# MCU.net
KiCad netlist of a schematic drawn in Altium Designer
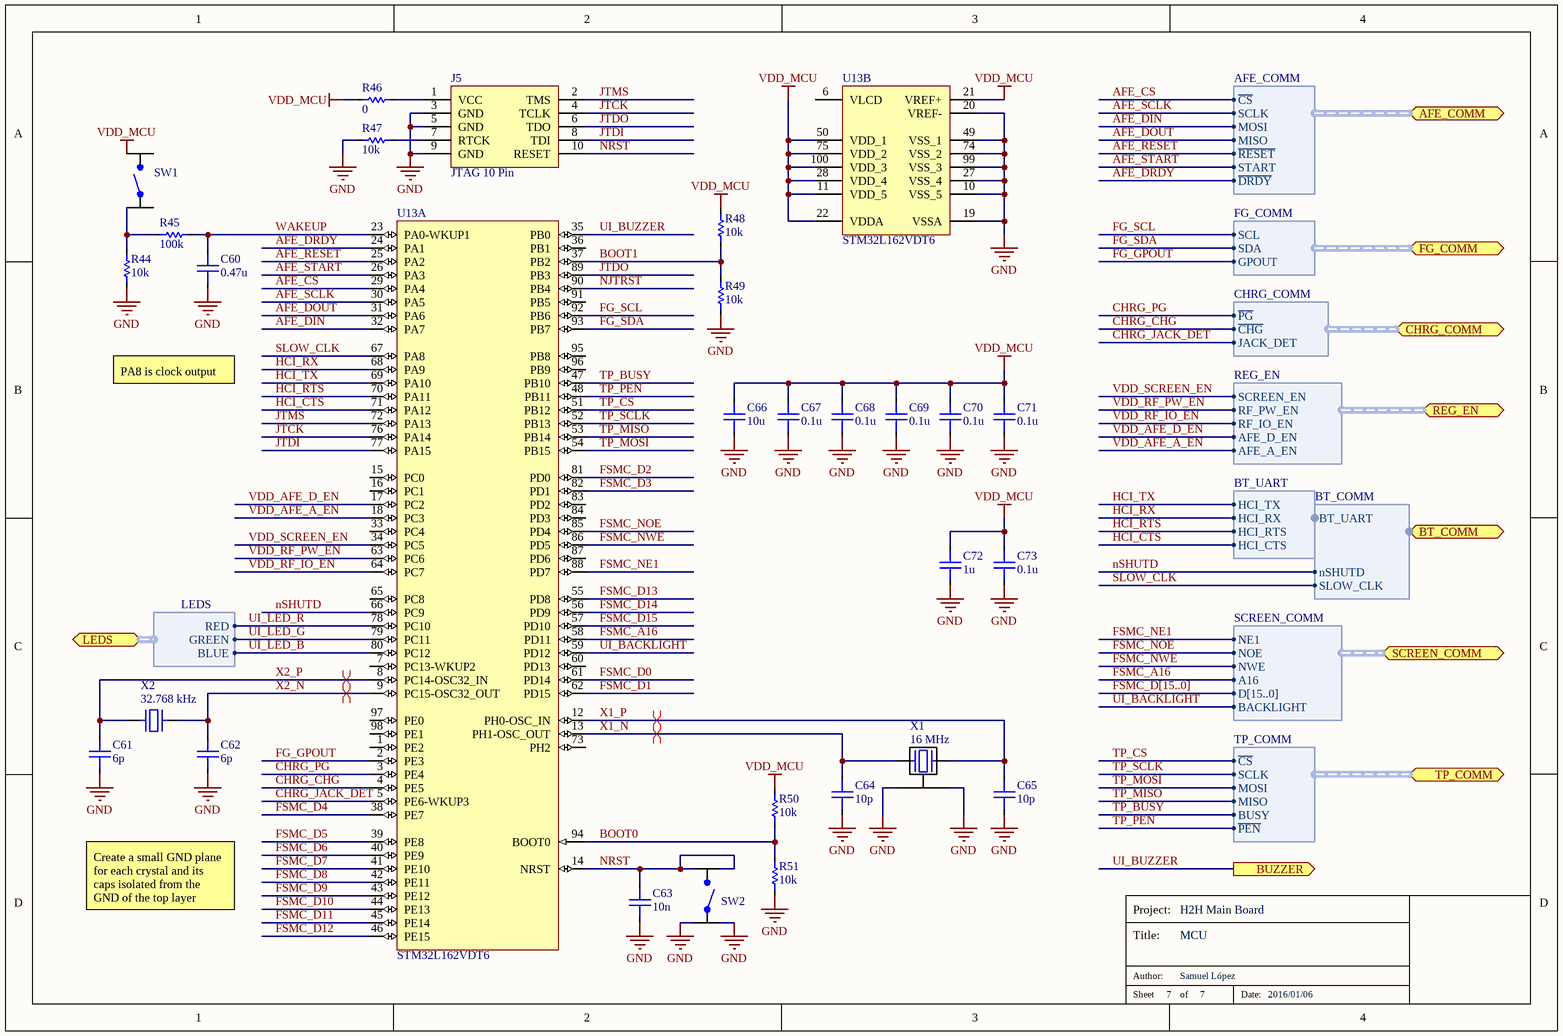
[diagram p0: MCU.SchDoc]

(export (version "E")
  (design (tool "Eeschema 10.0.6"))
  (components
    (comp (ref "C60")
      (value "0.47u")
      (footprint "C0603")
      (description "Capacitor")
      (libsource (lib "Misc") (part "Capacitor"))
    )
    (comp (ref "C61")
      (value "6p")
      (footprint "C0603")
      (description "Capacitor")
      (libsource (lib "Misc") (part "Capacitor"))
    )
    (comp (ref "C62")
      (value "6p")
      (footprint "C0603")
      (description "Capacitor")
      (libsource (lib "Misc") (part "Capacitor"))
    )
    (comp (ref "C63")
      (value "10n")
      (footprint "C0603")
      (description "Capacitor")
      (libsource (lib "Misc") (part "Capacitor"))
    )
    (comp (ref "C64")
      (value "10p")
      (footprint "C0603")
      (description "Capacitor")
      (libsource (lib "Misc") (part "Capacitor"))
    )
    (comp (ref "C65")
      (value "10p")
      (footprint "C0603")
      (description "Capacitor")
      (libsource (lib "Misc") (part "Capacitor"))
    )
    (comp (ref "C66")
      (value "10u")
      (footprint "C0603")
      (description "Capacitor")
      (libsource (lib "Misc") (part "Capacitor"))
    )
    (comp (ref "C67")
      (value "0.1u")
      (footprint "C0603")
      (description "Capacitor")
      (libsource (lib "Misc") (part "Capacitor"))
    )
    (comp (ref "C68")
      (value "0.1u")
      (footprint "C0603")
      (description "Capacitor")
      (libsource (lib "Misc") (part "Capacitor"))
    )
    (comp (ref "C69")
      (value "0.1u")
      (footprint "C0603")
      (description "Capacitor")
      (libsource (lib "Misc") (part "Capacitor"))
    )
    (comp (ref "C70")
      (value "0.1u")
      (footprint "C0603")
      (description "Capacitor")
      (libsource (lib "Misc") (part "Capacitor"))
    )
    (comp (ref "C71")
      (value "0.1u")
      (footprint "C0603")
      (description "Capacitor")
      (libsource (lib "Misc") (part "Capacitor"))
    )
    (comp (ref "C72")
      (value "1u")
      (footprint "C0603")
      (description "Capacitor")
      (libsource (lib "Misc") (part "Capacitor"))
    )
    (comp (ref "C73")
      (value "0.1u")
      (footprint "C0603")
      (description "Capacitor")
      (libsource (lib "Misc") (part "Capacitor"))
    )
    (comp (ref "J5")
      (value "JTAG 10 Pin")
      (footprint "3220-10-0200-00")
      (description "Conn - JTAG, Header, Male, Right Angle, 10 Pin, 1.27mm Pitch, ARM Standard")
      (libsource (lib "Conn") (part "3220-10-0200-00"))
    )
    (comp (ref "R44")
      (value "10k")
      (footprint "R0603")
      (description "Resistor")
      (libsource (lib "Misc") (part "Resistor"))
    )
    (comp (ref "R45")
      (value "100k")
      (footprint "R0603")
      (description "Resistor")
      (libsource (lib "Misc") (part "Resistor"))
    )
    (comp (ref "R46")
      (value "0")
      (footprint "R0603")
      (description "Resistor")
      (libsource (lib "Misc") (part "Resistor"))
    )
    (comp (ref "R47")
      (value "10k")
      (footprint "R0603")
      (description "Resistor")
      (libsource (lib "Misc") (part "Resistor"))
    )
    (comp (ref "R48")
      (value "10k")
      (footprint "R0603")
      (description "Resistor")
      (libsource (lib "Misc") (part "Resistor"))
    )
    (comp (ref "R49")
      (value "10k")
      (footprint "R0603")
      (description "Resistor")
      (libsource (lib "Misc") (part "Resistor"))
    )
    (comp (ref "R50")
      (value "10k")
      (footprint "R0603")
      (description "Resistor")
      (libsource (lib "Misc") (part "Resistor"))
    )
    (comp (ref "R51")
      (value "10k")
      (footprint "R0603")
      (description "Resistor")
      (libsource (lib "Misc") (part "Resistor"))
    )
    (comp (ref "SW1")
      (value "WS-TASU 436331045822")
      (footprint "WS-TASU 436331045822")
      (description "Switch - Tactile, Off-Mom, SPST, Side-Actuated")
      (libsource (lib "H2H") (part "WS-TASU 436331045822"))
    )
    (comp (ref "SW2")
      (value "EVQ-Q2K01W")
      (footprint "EVQ-Q2K01W")
      (description "Switch - Tactile, Off-Mom, SPST")
      (libsource (lib "H2H") (part "EVQ-Q2K01W"))
    )
    (comp (ref "U13")
      (value "STM32L162VDT6")
      (footprint "STM-LQFP100_N")
      (fields (field (name "MANUFACTURER") "STMicroelectronics"))
      (libsource (lib "STMicroelectronics STM32 L1") (part "STM32L162VDT6"))
    )
    (comp (ref "X1")
      (value "ABM3B-16.000MHZ-10-1-U")
      (footprint "ABM3B-16.000MHZ-10-1-U")
      (description "Crystal - 16 MHz")
      (fields (field (name "FREQUENCY") "16 MHz"))
      (libsource (lib "H2H") (part "ABM3B-16.000MHZ-10-1-U"))
    )
    (comp (ref "X2")
      (value "ABS07-120-32.768KHZ-T")
      (footprint "ABS07-120-32.768KHZ-T")
      (description "Crystal - 32.768 kHz")
      (fields (field (name "FREQUENCY") "32.768 kHz"))
      (libsource (lib "H2H") (part "ABS07-120-32.768KHZ-T"))
    )
  )
  (nets
    (net (code "9") (name "/AFE_CS") (class "Default")
      (node (ref "U13") (pin "29") (pinfunction "PA4_29") (pintype "bidirectional"))
    )
    (net (code "10") (name "/AFE_DIN") (class "Default")
      (node (ref "U13") (pin "32") (pinfunction "PA7_32") (pintype "bidirectional"))
    )
    (net (code "11") (name "/AFE_DOUT") (class "Default")
      (node (ref "U13") (pin "31") (pinfunction "PA6_31") (pintype "bidirectional"))
    )
    (net (code "12") (name "/AFE_DRDY") (class "Default")
      (node (ref "U13") (pin "24") (pinfunction "PA1_24") (pintype "bidirectional"))
    )
    (net (code "13") (name "/AFE_RESET") (class "Default")
      (node (ref "U13") (pin "25") (pinfunction "PA2_25") (pintype "bidirectional"))
    )
    (net (code "14") (name "/AFE_SCLK") (class "Default")
      (node (ref "U13") (pin "30") (pinfunction "PA5_30") (pintype "bidirectional"))
    )
    (net (code "15") (name "/AFE_START") (class "Default")
      (node (ref "U13") (pin "26") (pinfunction "PA3_26") (pintype "bidirectional"))
    )
    (net (code "16") (name "/BOOT0") (class "Default")
      (node (ref "R50") (pin "1") (pinfunction "1_1") (pintype "passive"))
      (node (ref "R51") (pin "2") (pinfunction "2_2") (pintype "passive"))
      (node (ref "U13") (pin "94") (pinfunction "BOOT0_94") (pintype "input"))
    )
    (net (code "17") (name "/BOOT1") (class "Default")
      (node (ref "R48") (pin "1") (pinfunction "1_1") (pintype "passive"))
      (node (ref "R49") (pin "2") (pinfunction "2_2") (pintype "passive"))
      (node (ref "U13") (pin "37") (pinfunction "PB2_37") (pintype "bidirectional"))
    )
    (net (code "18") (name "/CHRG_CHG") (class "Default")
      (node (ref "U13") (pin "4") (pinfunction "PE5_4") (pintype "bidirectional"))
    )
    (net (code "19") (name "/CHRG_JACK_DET") (class "Default")
      (node (ref "U13") (pin "5") (pinfunction "PE6-WKUP3_5") (pintype "bidirectional"))
    )
    (net (code "20") (name "/CHRG_PG") (class "Default")
      (node (ref "U13") (pin "3") (pinfunction "PE4_3") (pintype "bidirectional"))
    )
    (net (code "21") (name "/FG_GPOUT") (class "Default")
      (node (ref "U13") (pin "2") (pinfunction "PE3_2") (pintype "bidirectional"))
    )
    (net (code "22") (name "/FG_SCL") (class "Default")
      (node (ref "U13") (pin "92") (pinfunction "PB6_92") (pintype "bidirectional"))
    )
    (net (code "23") (name "/FG_SDA") (class "Default")
      (node (ref "U13") (pin "93") (pinfunction "PB7_93") (pintype "bidirectional"))
    )
    (net (code "24") (name "/FSMC_A16") (class "Default")
      (node (ref "U13") (pin "58") (pinfunction "PD11_58") (pintype "bidirectional"))
    )
    (net (code "25") (name "/FSMC_D0") (class "Default")
      (node (ref "U13") (pin "61") (pinfunction "PD14_61") (pintype "bidirectional"))
    )
    (net (code "26") (name "/FSMC_D1") (class "Default")
      (node (ref "U13") (pin "62") (pinfunction "PD15_62") (pintype "bidirectional"))
    )
    (net (code "27") (name "/FSMC_D2") (class "Default")
      (node (ref "U13") (pin "81") (pinfunction "PD0_81") (pintype "bidirectional"))
    )
    (net (code "28") (name "/FSMC_D3") (class "Default")
      (node (ref "U13") (pin "82") (pinfunction "PD1_82") (pintype "bidirectional"))
    )
    (net (code "29") (name "/FSMC_D4") (class "Default")
      (node (ref "U13") (pin "38") (pinfunction "PE7_38") (pintype "bidirectional"))
    )
    (net (code "30") (name "/FSMC_D5") (class "Default")
      (node (ref "U13") (pin "39") (pinfunction "PE8_39") (pintype "bidirectional"))
    )
    (net (code "31") (name "/FSMC_D6") (class "Default")
      (node (ref "U13") (pin "40") (pinfunction "PE9_40") (pintype "bidirectional"))
    )
    (net (code "32") (name "/FSMC_D7") (class "Default")
      (node (ref "U13") (pin "41") (pinfunction "PE10_41") (pintype "bidirectional"))
    )
    (net (code "33") (name "/FSMC_D8") (class "Default")
      (node (ref "U13") (pin "42") (pinfunction "PE11_42") (pintype "bidirectional"))
    )
    (net (code "34") (name "/FSMC_D9") (class "Default")
      (node (ref "U13") (pin "43") (pinfunction "PE12_43") (pintype "bidirectional"))
    )
    (net (code "35") (name "/FSMC_D10") (class "Default")
      (node (ref "U13") (pin "44") (pinfunction "PE13_44") (pintype "bidirectional"))
    )
    (net (code "36") (name "/FSMC_D11") (class "Default")
      (node (ref "U13") (pin "45") (pinfunction "PE14_45") (pintype "bidirectional"))
    )
    (net (code "37") (name "/FSMC_D12") (class "Default")
      (node (ref "U13") (pin "46") (pinfunction "PE15_46") (pintype "bidirectional"))
    )
    (net (code "38") (name "/FSMC_D13") (class "Default")
      (node (ref "U13") (pin "55") (pinfunction "PD8_55") (pintype "bidirectional"))
    )
    (net (code "39") (name "/FSMC_D14") (class "Default")
      (node (ref "U13") (pin "56") (pinfunction "PD9_56") (pintype "bidirectional"))
    )
    (net (code "40") (name "/FSMC_D15") (class "Default")
      (node (ref "U13") (pin "57") (pinfunction "PD10_57") (pintype "bidirectional"))
    )
    (net (code "41") (name "/FSMC_NE1") (class "Default")
      (node (ref "U13") (pin "88") (pinfunction "PD7_88") (pintype "bidirectional"))
    )
    (net (code "42") (name "/FSMC_NOE") (class "Default")
      (node (ref "U13") (pin "85") (pinfunction "PD4_85") (pintype "bidirectional"))
    )
    (net (code "43") (name "/FSMC_NWE") (class "Default")
      (node (ref "U13") (pin "86") (pinfunction "PD5_86") (pintype "bidirectional"))
    )
    (net (code "44") (name "/HCI_CTS") (class "Default")
      (node (ref "U13") (pin "71") (pinfunction "PA12_71") (pintype "bidirectional"))
    )
    (net (code "45") (name "/HCI_RTS") (class "Default")
      (node (ref "U13") (pin "70") (pinfunction "PA11_70") (pintype "bidirectional"))
    )
    (net (code "46") (name "/HCI_RX") (class "Default")
      (node (ref "U13") (pin "68") (pinfunction "PA9_68") (pintype "bidirectional"))
    )
    (net (code "47") (name "/HCI_TX") (class "Default")
      (node (ref "U13") (pin "69") (pinfunction "PA10_69") (pintype "bidirectional"))
    )
    (net (code "48") (name "/JTCK") (class "Default")
      (node (ref "J5") (pin "4") (pinfunction "TCLK_4") (pintype "passive"))
      (node (ref "U13") (pin "76") (pinfunction "PA14_76") (pintype "bidirectional"))
    )
    (net (code "49") (name "/JTDI") (class "Default")
      (node (ref "J5") (pin "8") (pinfunction "TDI_8") (pintype "passive"))
      (node (ref "U13") (pin "77") (pinfunction "PA15_77") (pintype "bidirectional"))
    )
    (net (code "50") (name "/JTDO") (class "Default")
      (node (ref "J5") (pin "6") (pinfunction "TDO_6") (pintype "passive"))
      (node (ref "U13") (pin "89") (pinfunction "PB3_89") (pintype "bidirectional"))
    )
    (net (code "51") (name "/JTMS") (class "Default")
      (node (ref "J5") (pin "2") (pinfunction "TMS_2") (pintype "passive"))
      (node (ref "U13") (pin "72") (pinfunction "PA13_72") (pintype "bidirectional"))
    )
    (net (code "52") (name "/NJTRST") (class "Default")
      (node (ref "U13") (pin "90") (pinfunction "PB4_90") (pintype "bidirectional"))
    )
    (net (code "53") (name "/NRST") (class "Default")
      (node (ref "C63") (pin "2") (pinfunction "2_2") (pintype "passive"))
      (node (ref "J5") (pin "10") (pinfunction "RESET_10") (pintype "passive"))
      (node (ref "SW2") (pin "3") (pinfunction "B2_3") (pintype "passive"))
      (node (ref "SW2") (pin "4") (pinfunction "B1_4") (pintype "passive"))
      (node (ref "U13") (pin "14") (pinfunction "NRST_14") (pintype "bidirectional"))
    )
    (net (code "55") (name "/SLOW_CLK") (class "Default")
      (node (ref "U13") (pin "67") (pinfunction "PA8_67") (pintype "bidirectional"))
    )
    (net (code "56") (name "/TP_BUSY") (class "Default")
      (node (ref "U13") (pin "47") (pinfunction "PB10_47") (pintype "bidirectional"))
    )
    (net (code "57") (name "/TP_CS") (class "Default")
      (node (ref "U13") (pin "51") (pinfunction "PB12_51") (pintype "bidirectional"))
    )
    (net (code "58") (name "/TP_MISO") (class "Default")
      (node (ref "U13") (pin "53") (pinfunction "PB14_53") (pintype "bidirectional"))
    )
    (net (code "59") (name "/TP_MOSI") (class "Default")
      (node (ref "U13") (pin "54") (pinfunction "PB15_54") (pintype "bidirectional"))
    )
    (net (code "60") (name "/TP_PEN") (class "Default")
      (node (ref "U13") (pin "48") (pinfunction "PB11_48") (pintype "bidirectional"))
    )
    (net (code "61") (name "/TP_SCLK") (class "Default")
      (node (ref "U13") (pin "52") (pinfunction "PB13_52") (pintype "bidirectional"))
    )
    (net (code "62") (name "/UI_BACKLIGHT") (class "Default")
      (node (ref "U13") (pin "59") (pinfunction "PD12_59") (pintype "bidirectional"))
    )
    (net (code "63") (name "/UI_BUZZER") (class "Default")
      (node (ref "U13") (pin "35") (pinfunction "PB0_35") (pintype "bidirectional"))
    )
    (net (code "64") (name "/UI_LED_B") (class "Default")
      (node (ref "U13") (pin "80") (pinfunction "PC12_80") (pintype "bidirectional"))
    )
    (net (code "65") (name "/UI_LED_G") (class "Default")
      (node (ref "U13") (pin "79") (pinfunction "PC11_79") (pintype "bidirectional"))
    )
    (net (code "66") (name "/UI_LED_R") (class "Default")
      (node (ref "U13") (pin "78") (pinfunction "PC10_78") (pintype "bidirectional"))
    )
    (net (code "67") (name "/VDD_AFE_A_EN") (class "Default")
      (node (ref "U13") (pin "18") (pinfunction "PC3_18") (pintype "bidirectional"))
    )
    (net (code "68") (name "/VDD_AFE_D_EN") (class "Default")
      (node (ref "U13") (pin "17") (pinfunction "PC2_17") (pintype "bidirectional"))
    )
    (net (code "69") (name "/VDD_RF_IO_EN") (class "Default")
      (node (ref "U13") (pin "64") (pinfunction "PC7_64") (pintype "bidirectional"))
    )
    (net (code "70") (name "/VDD_RF_PW_EN") (class "Default")
      (node (ref "U13") (pin "63") (pinfunction "PC6_63") (pintype "bidirectional"))
    )
    (net (code "71") (name "/VDD_SCREEN_EN") (class "Default")
      (node (ref "U13") (pin "34") (pinfunction "PC5_34") (pintype "bidirectional"))
    )
    (net (code "72") (name "/WAKEUP") (class "Default")
      (node (ref "C60") (pin "2") (pinfunction "2_2") (pintype "passive"))
      (node (ref "R45") (pin "2") (pinfunction "2_2") (pintype "passive"))
      (node (ref "U13") (pin "23") (pinfunction "PA0-WKUP1_23") (pintype "bidirectional"))
    )
    (net (code "73") (name "/X1_N") (class "Default")
      (node (ref "C64") (pin "2") (pinfunction "2_2") (pintype "passive"))
      (node (ref "U13") (pin "13") (pinfunction "PH1-OSC_OUT_13") (pintype "bidirectional"))
      (node (ref "X1") (pin "1") (pinfunction "1_1") (pintype "passive"))
    )
    (net (code "74") (name "/X1_P") (class "Default")
      (node (ref "C65") (pin "2") (pinfunction "2_2") (pintype "passive"))
      (node (ref "U13") (pin "12") (pinfunction "PH0-OSC_IN_12") (pintype "bidirectional"))
      (node (ref "X1") (pin "3") (pinfunction "3_3") (pintype "passive"))
    )
    (net (code "75") (name "/X2_N") (class "Default")
      (node (ref "C62") (pin "2") (pinfunction "2_2") (pintype "passive"))
      (node (ref "U13") (pin "9") (pinfunction "PC15-OSC32_OUT_9") (pintype "bidirectional"))
      (node (ref "X2") (pin "1") (pinfunction "1_1") (pintype "passive"))
    )
    (net (code "76") (name "/X2_P") (class "Default")
      (node (ref "C61") (pin "2") (pinfunction "2_2") (pintype "passive"))
      (node (ref "U13") (pin "8") (pinfunction "PC14-OSC32_IN_8") (pintype "bidirectional"))
      (node (ref "X2") (pin "2") (pinfunction "2_2") (pintype "passive"))
    )
    (net (code "77") (name "/nSHUTD") (class "Default")
      (node (ref "U13") (pin "66") (pinfunction "PC9_66") (pintype "bidirectional"))
    )
    (net (code "86") (name "GND") (class "Default")
      (node (ref "C60") (pin "1") (pinfunction "1_1") (pintype "passive"))
      (node (ref "C61") (pin "1") (pinfunction "1_1") (pintype "passive"))
      (node (ref "C62") (pin "1") (pinfunction "1_1") (pintype "passive"))
      (node (ref "C63") (pin "1") (pinfunction "1_1") (pintype "passive"))
      (node (ref "C64") (pin "1") (pinfunction "1_1") (pintype "passive"))
      (node (ref "C65") (pin "1") (pinfunction "1_1") (pintype "passive"))
      (node (ref "C66") (pin "1") (pinfunction "1_1") (pintype "passive"))
      (node (ref "C67") (pin "1") (pinfunction "1_1") (pintype "passive"))
      (node (ref "C68") (pin "1") (pinfunction "1_1") (pintype "passive"))
      (node (ref "C69") (pin "1") (pinfunction "1_1") (pintype "passive"))
      (node (ref "C70") (pin "1") (pinfunction "1_1") (pintype "passive"))
      (node (ref "C71") (pin "1") (pinfunction "1_1") (pintype "passive"))
      (node (ref "C72") (pin "1") (pinfunction "1_1") (pintype "passive"))
      (node (ref "C73") (pin "1") (pinfunction "1_1") (pintype "passive"))
      (node (ref "J5") (pin "3") (pinfunction "GND_3") (pintype "passive"))
      (node (ref "J5") (pin "5") (pinfunction "GND_5") (pintype "passive"))
      (node (ref "J5") (pin "9") (pinfunction "GND_9") (pintype "passive"))
      (node (ref "R44") (pin "1") (pinfunction "1_1") (pintype "passive"))
      (node (ref "R47") (pin "1") (pinfunction "1_1") (pintype "passive"))
      (node (ref "R49") (pin "1") (pinfunction "1_1") (pintype "passive"))
      (node (ref "R51") (pin "1") (pinfunction "1_1") (pintype "passive"))
      (node (ref "SW2") (pin "1") (pinfunction "A1_1") (pintype "passive"))
      (node (ref "SW2") (pin "2") (pinfunction "A2_2") (pintype "passive"))
      (node (ref "U13") (pin "10") (pinfunction "VSS_5_10") (pintype "power_in"))
      (node (ref "U13") (pin "19") (pinfunction "VSSA_19") (pintype "power_in"))
      (node (ref "U13") (pin "20") (pinfunction "VREF-_20") (pintype "power_in"))
      (node (ref "U13") (pin "27") (pinfunction "VSS_4_27") (pintype "power_in"))
      (node (ref "U13") (pin "49") (pinfunction "VSS_1_49") (pintype "power_in"))
      (node (ref "U13") (pin "74") (pinfunction "VSS_2_74") (pintype "power_in"))
      (node (ref "U13") (pin "99") (pinfunction "VSS_3_99") (pintype "power_in"))
      (node (ref "X1") (pin "2") (pinfunction "2_2") (pintype "passive"))
      (node (ref "X1") (pin "4") (pinfunction "4_4") (pintype "passive"))
    )
    (net (code "87") (name "Net-(J5-RTCK)") (class "Default")
      (node (ref "J5") (pin "7") (pinfunction "RTCK_7") (pintype "passive"))
      (node (ref "R47") (pin "2") (pinfunction "2_2") (pintype "passive"))
    )
    (net (code "88") (name "Net-(J5-VCC)") (class "Default")
      (node (ref "J5") (pin "1") (pinfunction "VCC_1") (pintype "passive"))
      (node (ref "R46") (pin "2") (pinfunction "2_2") (pintype "passive"))
    )
    (net (code "89") (name "Net-(R44-Pad2)") (class "Default")
      (node (ref "R44") (pin "2") (pinfunction "2_2") (pintype "passive"))
      (node (ref "R45") (pin "1") (pinfunction "1_1") (pintype "passive"))
      (node (ref "SW1") (pin "1") (pinfunction "1_1") (pintype "passive"))
    )
    (net (code "90") (name "VDD_MCU") (class "Default")
      (node (ref "C66") (pin "2") (pinfunction "2_2") (pintype "passive"))
      (node (ref "C67") (pin "2") (pinfunction "2_2") (pintype "passive"))
      (node (ref "C68") (pin "2") (pinfunction "2_2") (pintype "passive"))
      (node (ref "C69") (pin "2") (pinfunction "2_2") (pintype "passive"))
      (node (ref "C70") (pin "2") (pinfunction "2_2") (pintype "passive"))
      (node (ref "C71") (pin "2") (pinfunction "2_2") (pintype "passive"))
      (node (ref "C72") (pin "2") (pinfunction "2_2") (pintype "passive"))
      (node (ref "C73") (pin "2") (pinfunction "2_2") (pintype "passive"))
      (node (ref "R46") (pin "1") (pinfunction "1_1") (pintype "passive"))
      (node (ref "R48") (pin "2") (pinfunction "2_2") (pintype "passive"))
      (node (ref "R50") (pin "2") (pinfunction "2_2") (pintype "passive"))
      (node (ref "SW1") (pin "2") (pinfunction "2_2") (pintype "passive"))
      (node (ref "U13") (pin "100") (pinfunction "VDD_3_100") (pintype "power_in"))
      (node (ref "U13") (pin "11") (pinfunction "VDD_5_11") (pintype "power_in"))
      (node (ref "U13") (pin "21") (pinfunction "VREF+_21") (pintype "power_in"))
      (node (ref "U13") (pin "22") (pinfunction "VDDA_22") (pintype "power_in"))
      (node (ref "U13") (pin "28") (pinfunction "VDD_4_28") (pintype "power_in"))
      (node (ref "U13") (pin "50") (pinfunction "VDD_1_50") (pintype "power_in"))
      (node (ref "U13") (pin "75") (pinfunction "VDD_2_75") (pintype "power_in"))
    )
    (net (code "91") (name "unconnected-(SW1-Pad3)") (class "Default")
      (node (ref "SW1") (pin "3") (pinfunction "3_3") (pintype "passive"))
    )
    (net (code "92") (name "unconnected-(SW1-Pad4)") (class "Default")
      (node (ref "SW1") (pin "4") (pinfunction "4_4") (pintype "passive"))
    )
    (net (code "93") (name "unconnected-(U13A-PB1-Pad36)") (class "Default")
      (node (ref "U13") (pin "36") (pinfunction "PB1_36") (pintype "bidirectional"))
    )
    (net (code "94") (name "unconnected-(U13A-PB5-Pad91)") (class "Default")
      (node (ref "U13") (pin "91") (pinfunction "PB5_91") (pintype "bidirectional"))
    )
    (net (code "95") (name "unconnected-(U13A-PB8-Pad95)") (class "Default")
      (node (ref "U13") (pin "95") (pinfunction "PB8_95") (pintype "bidirectional"))
    )
    (net (code "96") (name "unconnected-(U13A-PB9-Pad96)") (class "Default")
      (node (ref "U13") (pin "96") (pinfunction "PB9_96") (pintype "bidirectional"))
    )
    (net (code "97") (name "unconnected-(U13A-PC0-Pad15)") (class "Default")
      (node (ref "U13") (pin "15") (pinfunction "PC0_15") (pintype "bidirectional"))
    )
    (net (code "98") (name "unconnected-(U13A-PC1-Pad16)") (class "Default")
      (node (ref "U13") (pin "16") (pinfunction "PC1_16") (pintype "bidirectional"))
    )
    (net (code "99") (name "unconnected-(U13A-PC4-Pad33)") (class "Default")
      (node (ref "U13") (pin "33") (pinfunction "PC4_33") (pintype "bidirectional"))
    )
    (net (code "100") (name "unconnected-(U13A-PC8-Pad65)") (class "Default")
      (node (ref "U13") (pin "65") (pinfunction "PC8_65") (pintype "bidirectional"))
    )
    (net (code "101") (name "unconnected-(U13A-PC13-WKUP2-Pad7)") (class "Default")
      (node (ref "U13") (pin "7") (pinfunction "PC13-WKUP2_7") (pintype "bidirectional"))
    )
    (net (code "102") (name "unconnected-(U13A-PD2-Pad83)") (class "Default")
      (node (ref "U13") (pin "83") (pinfunction "PD2_83") (pintype "bidirectional"))
    )
    (net (code "103") (name "unconnected-(U13A-PD3-Pad84)") (class "Default")
      (node (ref "U13") (pin "84") (pinfunction "PD3_84") (pintype "bidirectional"))
    )
    (net (code "104") (name "unconnected-(U13A-PD6-Pad87)") (class "Default")
      (node (ref "U13") (pin "87") (pinfunction "PD6_87") (pintype "bidirectional"))
    )
    (net (code "105") (name "unconnected-(U13A-PD13-Pad60)") (class "Default")
      (node (ref "U13") (pin "60") (pinfunction "PD13_60") (pintype "bidirectional"))
    )
    (net (code "106") (name "unconnected-(U13A-PE0-Pad97)") (class "Default")
      (node (ref "U13") (pin "97") (pinfunction "PE0_97") (pintype "bidirectional"))
    )
    (net (code "107") (name "unconnected-(U13A-PE1-Pad98)") (class "Default")
      (node (ref "U13") (pin "98") (pinfunction "PE1_98") (pintype "bidirectional"))
    )
    (net (code "108") (name "unconnected-(U13A-PE2-Pad1)") (class "Default")
      (node (ref "U13") (pin "1") (pinfunction "PE2_1") (pintype "bidirectional"))
    )
    (net (code "109") (name "unconnected-(U13A-PH2-Pad73)") (class "Default")
      (node (ref "U13") (pin "73") (pinfunction "PH2_73") (pintype "bidirectional"))
    )
    (net (code "110") (name "unconnected-(U13B-VLCD-Pad6)") (class "Default")
      (node (ref "U13") (pin "6") (pinfunction "VLCD_6") (pintype "power_in"))
    )
  )
)
